# ProPrj_PocketEPD.net
KiCad netlist of a schematic drawn in EasyEDA Pro
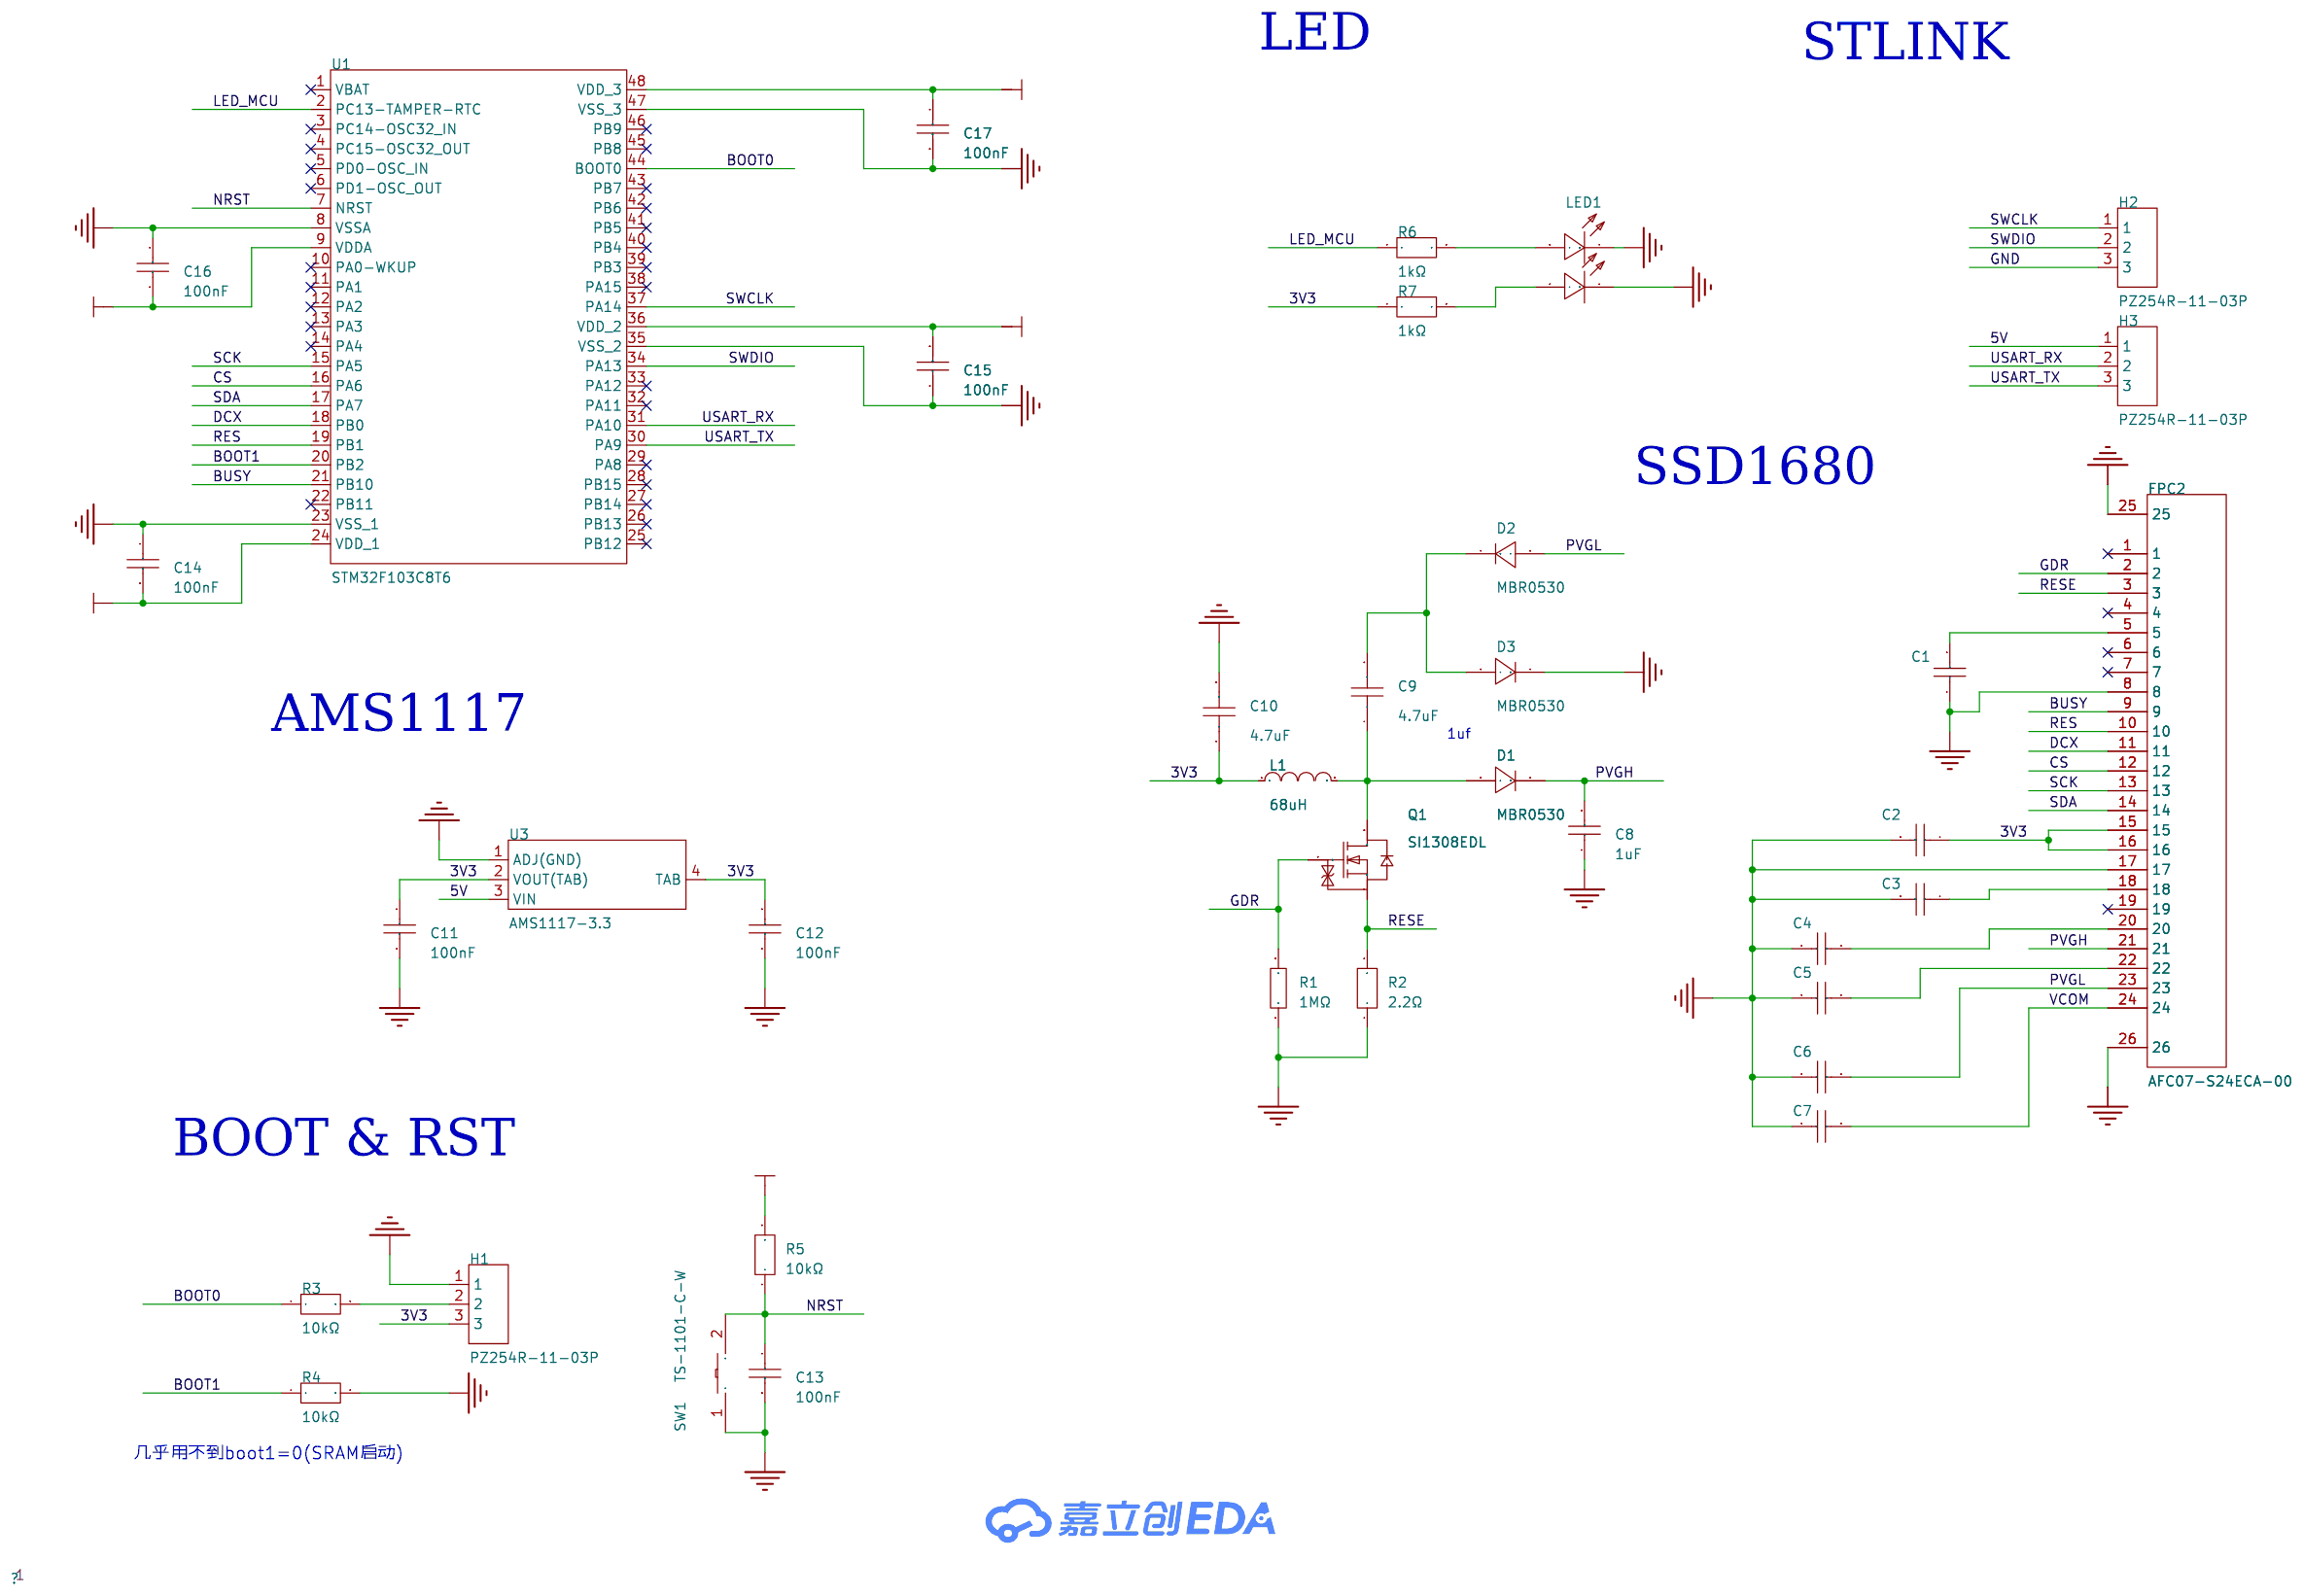
[diagram p0: schematic sheet]

(export (version "E")
  (design (tool "Eeschema 10.0.6"))
  (components
    (comp (ref "C1")
      (value "1uF")
      (footprint "easyedapro:C1206")
      (description "容值:1uF;精度:±10%;额定电压:25V;温度系数:X7R;")
      (fields
        (field (name "Manufacturer Part") "CL31B105KAHNNNE")
        (field (name "Manufacturer") "SAMSUNG(三星)")
      )
      (libsource (lib "easyedapro") (part "CL31B105KAHNNNE"))
    )
    (comp (ref "C2")
      (value "1uF")
      (footprint "easyedapro:C1206")
      (description "容值:1uF;精度:±10%;额定电压:25V;温度系数:X7R;")
      (fields
        (field (name "Manufacturer Part") "CL31B105KAHNNNE")
        (field (name "Manufacturer") "SAMSUNG(三星)")
      )
      (libsource (lib "easyedapro") (part "CL31B105KAHNNNE"))
    )
    (comp (ref "C3")
      (value "1uF")
      (footprint "easyedapro:C1206")
      (description "容值:1uF;精度:±10%;额定电压:25V;温度系数:X7R;")
      (fields
        (field (name "Manufacturer Part") "CL31B105KAHNNNE")
        (field (name "Manufacturer") "SAMSUNG(三星)")
      )
      (libsource (lib "easyedapro") (part "CL31B105KAHNNNE"))
    )
    (comp (ref "C4")
      (value "1uF")
      (footprint "easyedapro:C1206")
      (description "容值:1uF;精度:±10%;额定电压:25V;温度系数:X7R;")
      (fields
        (field (name "Manufacturer Part") "CL31B105KAHNNNE")
        (field (name "Manufacturer") "SAMSUNG(三星)")
      )
      (libsource (lib "easyedapro") (part "CL31B105KAHNNNE"))
    )
    (comp (ref "C5")
      (value "1uF")
      (footprint "easyedapro:C1206")
      (description "容值:1uF;精度:±10%;额定电压:25V;温度系数:X7R;")
      (fields
        (field (name "Manufacturer Part") "CL31B105KAHNNNE")
        (field (name "Manufacturer") "SAMSUNG(三星)")
      )
      (libsource (lib "easyedapro") (part "CL31B105KAHNNNE"))
    )
    (comp (ref "C6")
      (value "1uF")
      (footprint "easyedapro:C1206")
      (description "容值:1uF;精度:±10%;额定电压:25V;温度系数:X7R;")
      (fields
        (field (name "Manufacturer Part") "CL31B105KAHNNNE")
        (field (name "Manufacturer") "SAMSUNG(三星)")
      )
      (libsource (lib "easyedapro") (part "CL31B105KAHNNNE"))
    )
    (comp (ref "C7")
      (value "1uF")
      (footprint "easyedapro:C1206")
      (description "容值:1uF;精度:±10%;额定电压:25V;温度系数:X7R;")
      (fields
        (field (name "Manufacturer Part") "CL31B105KAHNNNE")
        (field (name "Manufacturer") "SAMSUNG(三星)")
      )
      (libsource (lib "easyedapro") (part "CL31B105KAHNNNE"))
    )
    (comp (ref "C8")
      (value "1uF")
      (footprint "easyedapro:C1206")
      (description "容值:1uF;精度:±10%;额定电压:25V;温度系数:X7R;")
      (fields
        (field (name "Manufacturer Part") "CL31B105KAHNNNE")
        (field (name "Manufacturer") "SAMSUNG(三星)")
      )
      (libsource (lib "easyedapro") (part "CL31B105KAHNNNE"))
    )
    (comp (ref "C9")
      (value "4.7uF")
      (footprint "easyedapro:C1206")
      (description "容值:4.7uF;精度:±10%;额定电压:25V;温度系数:X7R;")
      (fields (field (name "Manufacturer Part") "1206B475K250NT") (field (name "Manufacturer") "FH(风华)"))
      (libsource (lib "easyedapro") (part "1206B475K250NT"))
    )
    (comp (ref "C10")
      (value "4.7uF")
      (footprint "easyedapro:C1206")
      (description "容值:4.7uF;精度:±10%;额定电压:25V;温度系数:X7R;")
      (fields (field (name "Manufacturer Part") "1206B475K250NT") (field (name "Manufacturer") "FH(风华)"))
      (libsource (lib "easyedapro") (part "1206B475K250NT"))
    )
    (comp (ref "C11")
      (value "100nF")
      (footprint "easyedapro:C1206")
      (description "容值:100nF;精度:±10%;额定电压:100V;温度系数:X7R;")
      (fields
        (field (name "Manufacturer Part") "CL31B104KCFNNNE")
        (field (name "Manufacturer") "SAMSUNG(三星)")
      )
      (libsource (lib "easyedapro") (part "CL31B104KCFNNNE"))
    )
    (comp (ref "C12")
      (value "100nF")
      (footprint "easyedapro:C1206")
      (description "容值:100nF;精度:±10%;额定电压:100V;温度系数:X7R;")
      (fields
        (field (name "Manufacturer Part") "CL31B104KCFNNNE")
        (field (name "Manufacturer") "SAMSUNG(三星)")
      )
      (libsource (lib "easyedapro") (part "CL31B104KCFNNNE"))
    )
    (comp (ref "C13")
      (value "100nF")
      (footprint "easyedapro:C1206")
      (description "容值:100nF;精度:±10%;额定电压:100V;温度系数:X7R;")
      (fields
        (field (name "Manufacturer Part") "CL31B104KCFNNNE")
        (field (name "Manufacturer") "SAMSUNG(三星)")
      )
      (libsource (lib "easyedapro") (part "CL31B104KCFNNNE"))
    )
    (comp (ref "C14")
      (value "100nF")
      (footprint "easyedapro:C1206")
      (description "容值:100nF;精度:±10%;额定电压:100V;温度系数:X7R;")
      (fields
        (field (name "Manufacturer Part") "CL31B104KCFNNNE")
        (field (name "Manufacturer") "SAMSUNG(三星)")
      )
      (libsource (lib "easyedapro") (part "CL31B104KCFNNNE"))
    )
    (comp (ref "C15")
      (value "100nF")
      (footprint "easyedapro:C1206")
      (description "容值:100nF;精度:±10%;额定电压:100V;温度系数:X7R;")
      (fields
        (field (name "Manufacturer Part") "CL31B104KCFNNNE")
        (field (name "Manufacturer") "SAMSUNG(三星)")
      )
      (libsource (lib "easyedapro") (part "CL31B104KCFNNNE"))
    )
    (comp (ref "C16")
      (value "100nF")
      (footprint "easyedapro:C1206")
      (description "容值:100nF;精度:±10%;额定电压:100V;温度系数:X7R;")
      (fields
        (field (name "Manufacturer Part") "CL31B104KCFNNNE")
        (field (name "Manufacturer") "SAMSUNG(三星)")
      )
      (libsource (lib "easyedapro") (part "CL31B104KCFNNNE"))
    )
    (comp (ref "C17")
      (value "100nF")
      (footprint "easyedapro:C1206")
      (description "容值:100nF;精度:±10%;额定电压:100V;温度系数:X7R;")
      (fields
        (field (name "Manufacturer Part") "CL31B104KCFNNNE")
        (field (name "Manufacturer") "SAMSUNG(三星)")
      )
      (libsource (lib "easyedapro") (part "CL31B104KCFNNNE"))
    )
    (comp (ref "D1")
      (value "MBR0530")
      (footprint "easyedapro:SOD-123_L2.8-W1.8-LS3.7-RD")
      (description "二极管配置:-;正向压降(Vf):550mV@500mA;直流反向耐压(Vr):30V;整流电流:500mA;")
      (fields (field (name "Manufacturer") "CJ(江苏长电/长晶)"))
      (libsource (lib "easyedapro") (part "MBR0530"))
    )
    (comp (ref "D2")
      (value "MBR0530")
      (footprint "easyedapro:SOD-123_L2.8-W1.8-LS3.7-RD")
      (description "二极管配置:-;正向压降(Vf):550mV@500mA;直流反向耐压(Vr):30V;整流电流:500mA;")
      (fields (field (name "Manufacturer") "CJ(江苏长电/长晶)"))
      (libsource (lib "easyedapro") (part "MBR0530"))
    )
    (comp (ref "D3")
      (value "MBR0530")
      (footprint "easyedapro:SOD-123_L2.8-W1.8-LS3.7-RD")
      (description "二极管配置:-;正向压降(Vf):550mV@500mA;直流反向耐压(Vr):30V;整流电流:500mA;")
      (fields (field (name "Manufacturer") "CJ(江苏长电/长晶)"))
      (libsource (lib "easyedapro") (part "MBR0530"))
    )
    (comp (ref "FPC2")
      (value "AFC07-S24ECA-00")
      (footprint "easyedapro:FPC-SMD_AFC07-S24ECA-00")
      (description "锁定特性:抽屉式;触点类型:上接;触点数量:24P;间距:0.5mm;安装类型:卧贴;")
      (fields (field (name "Manufacturer") "JS(钜硕电子)"))
      (libsource (lib "easyedapro") (part "AFC07-S24ECA-00"))
    )
    (comp (ref "H1")
      (value "PZ254R-11-03P")
      (footprint "easyedapro:HDR-TH_3P-P2.54-H-M-W10.4")
      (fields (field (name "Manufacturer") "XFCN(兴飞)"))
      (libsource (lib "easyedapro") (part "PZ254R-11-03P"))
    )
    (comp (ref "H2")
      (value "PZ254R-11-03P")
      (footprint "easyedapro:HDR-TH_3P-P2.54-H-M-W10.4")
      (fields (field (name "Manufacturer") "XFCN(兴飞)"))
      (libsource (lib "easyedapro") (part "PZ254R-11-03P"))
    )
    (comp (ref "H3")
      (value "PZ254R-11-03P")
      (footprint "easyedapro:HDR-TH_3P-P2.54-H-M-W10.4")
      (fields (field (name "Manufacturer") "XFCN(兴飞)"))
      (libsource (lib "easyedapro") (part "PZ254R-11-03P"))
    )
    (comp (ref "L1")
      (value "68uH")
      (footprint "easyedapro:IND-SMD_L4.0-W4.0_FNR40XXS")
      (description "电感值:68uH;精度:±20%;额定电流:500mA;饱和电流(Isat):670mA;类型:磁胶屏蔽绕线合金电感;")
      (fields (field (name "Manufacturer Part") "FNR4020S680MT") (field (name "Manufacturer") "cjiang(长江微电)"))
      (libsource (lib "easyedapro") (part "FNR4020S680MT"))
    )
    (comp (ref "LED1")
      (value "TJ-S3227SW1TCGLC2R6B-A5")
      (footprint "easyedapro:LED-SMD_4P-L3.2-W2.7_PD15-22C")
      (fields (field (name "Manufacturer") "TOGIALED(统佳)"))
      (libsource (lib "easyedapro") (part "TJ-S3227SW1TCGLC2R6B-A5"))
    )
    (comp (ref "Q1")
      (value "SI1308EDL")
      (footprint "easyedapro:SOT-323-3_L2.0-W1.3-P1.30-LS2.1-BR")
      (description "漏源电压(Vdss):30V;连续漏极电流(Id):1.4A;导通电阻(RDS(on)):150mΩ@4.5V,0.5A;耗散功率(Pd):360mW;阈值电压(Vgs(th)):1.5V;")
      (fields (field (name "Manufacturer") "TECH PUBLIC(台舟)"))
      (libsource (lib "easyedapro") (part "SI1308EDL_C7603347"))
    )
    (comp (ref "R1")
      (value "1MΩ")
      (footprint "easyedapro:R1206")
      (description "电阻类型:厚膜电阻;阻值:1MΩ;精度:±5%;功率:250mW;工作电压:200V;温度系数:±100ppm/°C;")
      (fields (field (name "Manufacturer Part") "FRC1206J105 TS") (field (name "Manufacturer") "FOJAN(富捷)"))
      (libsource (lib "easyedapro") (part "FRC1206J105 TS"))
    )
    (comp (ref "R2")
      (value "2.2Ω")
      (footprint "easyedapro:R1206")
      (description "电阻类型:厚膜电阻;阻值:2.2Ω;精度:±5%;功率:250mW;工作电压:200V;温度系数:±200ppm/°C;")
      (fields (field (name "Manufacturer Part") "FRC1206J2R2 TS") (field (name "Manufacturer") "FOJAN(富捷)"))
      (libsource (lib "easyedapro") (part "FRC1206J2R2 TS"))
    )
    (comp (ref "R3")
      (value "10kΩ")
      (footprint "easyedapro:R1206")
      (description "电阻类型:厚膜电阻;阻值:10kΩ;精度:±5%;功率:250mW;工作电压:200V;温度系数:±100ppm/°C;")
      (fields (field (name "Manufacturer Part") "FRC1206J103 TS") (field (name "Manufacturer") "FOJAN(富捷)"))
      (libsource (lib "easyedapro") (part "FRC1206J103 TS"))
    )
    (comp (ref "R4")
      (value "10kΩ")
      (footprint "easyedapro:R1206")
      (description "电阻类型:厚膜电阻;阻值:10kΩ;精度:±5%;功率:250mW;工作电压:200V;温度系数:±100ppm/°C;")
      (fields (field (name "Manufacturer Part") "FRC1206J103 TS") (field (name "Manufacturer") "FOJAN(富捷)"))
      (libsource (lib "easyedapro") (part "FRC1206J103 TS"))
    )
    (comp (ref "R5")
      (value "10kΩ")
      (footprint "easyedapro:R1206")
      (description "电阻类型:厚膜电阻;阻值:10kΩ;精度:±5%;功率:250mW;工作电压:200V;温度系数:±100ppm/°C;")
      (fields (field (name "Manufacturer Part") "FRC1206J103 TS") (field (name "Manufacturer") "FOJAN(富捷)"))
      (libsource (lib "easyedapro") (part "FRC1206J103 TS"))
    )
    (comp (ref "R6")
      (value "1kΩ")
      (footprint "easyedapro:R1206")
      (description "电阻类型:厚膜电阻;阻值:1kΩ;精度:±5%;功率:250mW;工作电压:200V;温度系数:±100ppm/°C;")
      (fields (field (name "Manufacturer Part") "FRC1206J102 TS") (field (name "Manufacturer") "FOJAN(富捷)"))
      (libsource (lib "easyedapro") (part "FRC1206J102 TS"))
    )
    (comp (ref "R7")
      (value "1kΩ")
      (footprint "easyedapro:R1206")
      (description "电阻类型:厚膜电阻;阻值:1kΩ;精度:±5%;功率:250mW;工作电压:200V;温度系数:±100ppm/°C;")
      (fields (field (name "Manufacturer Part") "FRC1206J102 TS") (field (name "Manufacturer") "FOJAN(富捷)"))
      (libsource (lib "easyedapro") (part "FRC1206J102 TS"))
    )
    (comp (ref "SW1")
      (value "TS-1101-C-W")
      (footprint "easyedapro:SW-SMD_L6.0-W3.3-LS8.0")
      (fields (field (name "Manufacturer") "XKB Connectivity(中国星坤)"))
      (libsource (lib "easyedapro") (part "TS-1101-C-W"))
    )
    (comp (ref "U1")
      (value "STM32F103C8T6")
      (footprint "easyedapro:LQFP-48_L7.0-W7.0-P0.50-LS9.0-BL")
      (description "CPU内核:ARM-M3;CPU最大主频:72MHz;应用领域:-;")
      (fields (field (name "Manufacturer") "ST(意法半导体)"))
      (libsource (lib "easyedapro") (part "STM32F103C8T6"))
    )
    (comp (ref "U3")
      (value "AMS1117-3.3")
      (footprint "easyedapro:SOT-223-4_L6.5-W3.5-P2.30-LS7.0-BR")
      (description "输出类型:固定;工作电压:12V;输出电压:3.3V;输出电流:1A;电源纹波抑制比(PSRR):60dB@(120Hz);输出极性:正极;")
      (fields (field (name "Manufacturer") "UMW(友台半导体)"))
      (libsource (lib "easyedapro") (part "AMS1117-3.3_C347222"))
    )
  )
  (nets
    (net (code "1") (name "/5V") (class "Default")
      (node (ref "H3") (pin "1") (pinfunction "1_1") (pintype "unspecified"))
      (node (ref "U3") (pin "3") (pinfunction "VIN_3") (pintype "unspecified"))
    )
    (net (code "2") (name "/BOOT0") (class "Default")
      (node (ref "R3") (pin "1") (pinfunction "1_1") (pintype "unspecified"))
      (node (ref "U1") (pin "44") (pinfunction "BOOT0_44") (pintype "unspecified"))
    )
    (net (code "3") (name "/BOOT1") (class "Default")
      (node (ref "R4") (pin "1") (pinfunction "1_1") (pintype "unspecified"))
      (node (ref "U1") (pin "20") (pinfunction "PB2_20") (pintype "unspecified"))
    )
    (net (code "4") (name "/BUSY") (class "Default")
      (node (ref "FPC2") (pin "9") (pinfunction "9_9") (pintype "unspecified"))
      (node (ref "U1") (pin "21") (pinfunction "PB10_21") (pintype "unspecified"))
    )
    (net (code "5") (name "/CS") (class "Default")
      (node (ref "FPC2") (pin "12") (pinfunction "12_12") (pintype "unspecified"))
      (node (ref "U1") (pin "16") (pinfunction "PA6_16") (pintype "unspecified"))
    )
    (net (code "6") (name "/DCX") (class "Default")
      (node (ref "FPC2") (pin "11") (pinfunction "11_11") (pintype "unspecified"))
      (node (ref "U1") (pin "18") (pinfunction "PB0_18") (pintype "unspecified"))
    )
    (net (code "7") (name "/GDR") (class "Default")
      (node (ref "FPC2") (pin "2") (pinfunction "2_2") (pintype "unspecified"))
      (node (ref "Q1") (pin "1") (pinfunction "G_1") (pintype "unspecified"))
      (node (ref "R1") (pin "2") (pinfunction "2_2") (pintype "unspecified"))
    )
    (net (code "8") (name "/LED_MCU") (class "Default")
      (node (ref "R6") (pin "1") (pinfunction "1_1") (pintype "unspecified"))
      (node (ref "U1") (pin "2") (pinfunction "PC13-TAMPER-RTC_2") (pintype "unspecified"))
    )
    (net (code "9") (name "/NRST") (class "Default")
      (node (ref "C13") (pin "1") (pinfunction "1_1") (pintype "input"))
      (node (ref "R5") (pin "1") (pinfunction "1_1") (pintype "unspecified"))
      (node (ref "SW1") (pin "2") (pinfunction "2_2") (pintype "unspecified"))
      (node (ref "U1") (pin "7") (pinfunction "NRST_7") (pintype "unspecified"))
    )
    (net (code "10") (name "/PVGH") (class "Default")
      (node (ref "C8") (pin "2") (pinfunction "2_2") (pintype "input"))
      (node (ref "D1") (pin "1") (pinfunction "C_1") (pintype "unspecified"))
      (node (ref "FPC2") (pin "21") (pinfunction "21_21") (pintype "unspecified"))
    )
    (net (code "11") (name "/PVGL") (class "Default")
      (node (ref "C6") (pin "1") (pinfunction "1_1") (pintype "input"))
      (node (ref "D2") (pin "2") (pinfunction "A_2") (pintype "unspecified"))
      (node (ref "FPC2") (pin "23") (pinfunction "23_23") (pintype "unspecified"))
    )
    (net (code "12") (name "/RES") (class "Default")
      (node (ref "FPC2") (pin "10") (pinfunction "10_10") (pintype "unspecified"))
      (node (ref "U1") (pin "19") (pinfunction "PB1_19") (pintype "unspecified"))
    )
    (net (code "13") (name "/RESE") (class "Default")
      (node (ref "FPC2") (pin "3") (pinfunction "3_3") (pintype "unspecified"))
      (node (ref "Q1") (pin "2") (pinfunction "S_2") (pintype "unspecified"))
      (node (ref "R2") (pin "2") (pinfunction "2_2") (pintype "unspecified"))
    )
    (net (code "14") (name "/SCK") (class "Default")
      (node (ref "FPC2") (pin "13") (pinfunction "13_13") (pintype "unspecified"))
      (node (ref "U1") (pin "15") (pinfunction "PA5_15") (pintype "unspecified"))
    )
    (net (code "15") (name "/SDA") (class "Default")
      (node (ref "FPC2") (pin "14") (pinfunction "14_14") (pintype "unspecified"))
      (node (ref "U1") (pin "17") (pinfunction "PA7_17") (pintype "unspecified"))
    )
    (net (code "16") (name "/SWCLK") (class "Default")
      (node (ref "H2") (pin "1") (pinfunction "1_1") (pintype "unspecified"))
      (node (ref "U1") (pin "37") (pinfunction "PA14_37") (pintype "unspecified"))
    )
    (net (code "17") (name "/SWDIO") (class "Default")
      (node (ref "H2") (pin "2") (pinfunction "2_2") (pintype "unspecified"))
      (node (ref "U1") (pin "34") (pinfunction "PA13_34") (pintype "unspecified"))
    )
    (net (code "18") (name "/USART_RX") (class "Default")
      (node (ref "H3") (pin "2") (pinfunction "2_2") (pintype "unspecified"))
      (node (ref "U1") (pin "31") (pinfunction "PA10_31") (pintype "unspecified"))
    )
    (net (code "19") (name "/USART_TX") (class "Default")
      (node (ref "H3") (pin "3") (pinfunction "3_3") (pintype "unspecified"))
      (node (ref "U1") (pin "30") (pinfunction "PA9_30") (pintype "unspecified"))
    )
    (net (code "20") (name "/VCOM") (class "Default")
      (node (ref "C7") (pin "1") (pinfunction "1_1") (pintype "input"))
      (node (ref "FPC2") (pin "24") (pinfunction "24_24") (pintype "unspecified"))
    )
    (net (code "21") (name "3V3") (class "Default")
      (node (ref "C10") (pin "1") (pinfunction "1_1") (pintype "unspecified"))
      (node (ref "C11") (pin "2") (pinfunction "2_2") (pintype "input"))
      (node (ref "C12") (pin "2") (pinfunction "2_2") (pintype "input"))
      (node (ref "C14") (pin "2") (pinfunction "2_2") (pintype "input"))
      (node (ref "C15") (pin "2") (pinfunction "2_2") (pintype "input"))
      (node (ref "C16") (pin "2") (pinfunction "2_2") (pintype "input"))
      (node (ref "C17") (pin "1") (pinfunction "1_1") (pintype "input"))
      (node (ref "C2") (pin "1") (pinfunction "1_1") (pintype "input"))
      (node (ref "FPC2") (pin "15") (pinfunction "15_15") (pintype "unspecified"))
      (node (ref "FPC2") (pin "16") (pinfunction "16_16") (pintype "unspecified"))
      (node (ref "H1") (pin "3") (pinfunction "3_3") (pintype "unspecified"))
      (node (ref "L1") (pin "1") (pinfunction "1_1") (pintype "unspecified"))
      (node (ref "R5") (pin "2") (pinfunction "2_2") (pintype "unspecified"))
      (node (ref "R7") (pin "1") (pinfunction "1_1") (pintype "unspecified"))
      (node (ref "U1") (pin "24") (pinfunction "VDD_1_24") (pintype "unspecified"))
      (node (ref "U1") (pin "36") (pinfunction "VDD_2_36") (pintype "unspecified"))
      (node (ref "U1") (pin "48") (pinfunction "VDD_3_48") (pintype "unspecified"))
      (node (ref "U1") (pin "9") (pinfunction "VDDA_9") (pintype "unspecified"))
      (node (ref "U3") (pin "2") (pinfunction "VOUT(TAB)_2") (pintype "unspecified"))
      (node (ref "U3") (pin "4") (pinfunction "TAB_4") (pintype "unspecified"))
    )
    (net (code "22") (name "GND") (class "Default")
      (node (ref "C1") (pin "1") (pinfunction "1_1") (pintype "input"))
      (node (ref "C10") (pin "2") (pinfunction "2_2") (pintype "unspecified"))
      (node (ref "C11") (pin "1") (pinfunction "1_1") (pintype "input"))
      (node (ref "C12") (pin "1") (pinfunction "1_1") (pintype "input"))
      (node (ref "C13") (pin "2") (pinfunction "2_2") (pintype "input"))
      (node (ref "C14") (pin "1") (pinfunction "1_1") (pintype "input"))
      (node (ref "C15") (pin "1") (pinfunction "1_1") (pintype "input"))
      (node (ref "C16") (pin "1") (pinfunction "1_1") (pintype "input"))
      (node (ref "C17") (pin "2") (pinfunction "2_2") (pintype "input"))
      (node (ref "C2") (pin "2") (pinfunction "2_2") (pintype "input"))
      (node (ref "C3") (pin "2") (pinfunction "2_2") (pintype "input"))
      (node (ref "C4") (pin "2") (pinfunction "2_2") (pintype "input"))
      (node (ref "C5") (pin "2") (pinfunction "2_2") (pintype "input"))
      (node (ref "C6") (pin "2") (pinfunction "2_2") (pintype "input"))
      (node (ref "C7") (pin "2") (pinfunction "2_2") (pintype "input"))
      (node (ref "C8") (pin "1") (pinfunction "1_1") (pintype "input"))
      (node (ref "D3") (pin "1") (pinfunction "C_1") (pintype "unspecified"))
      (node (ref "FPC2") (pin "17") (pinfunction "17_17") (pintype "unspecified"))
      (node (ref "FPC2") (pin "25") (pinfunction "25_25") (pintype "unspecified"))
      (node (ref "FPC2") (pin "26") (pinfunction "26_26") (pintype "unspecified"))
      (node (ref "FPC2") (pin "8") (pinfunction "8_8") (pintype "unspecified"))
      (node (ref "H1") (pin "1") (pinfunction "1_1") (pintype "unspecified"))
      (node (ref "H2") (pin "3") (pinfunction "3_3") (pintype "unspecified"))
      (node (ref "LED1") (pin "1") (pinfunction "C_1") (pintype "unspecified"))
      (node (ref "LED1") (pin "4") (pinfunction "C_4") (pintype "unspecified"))
      (node (ref "R1") (pin "1") (pinfunction "1_1") (pintype "unspecified"))
      (node (ref "R2") (pin "1") (pinfunction "1_1") (pintype "unspecified"))
      (node (ref "R4") (pin "2") (pinfunction "2_2") (pintype "unspecified"))
      (node (ref "SW1") (pin "1") (pinfunction "1_1") (pintype "unspecified"))
      (node (ref "U1") (pin "23") (pinfunction "VSS_1_23") (pintype "unspecified"))
      (node (ref "U1") (pin "35") (pinfunction "VSS_2_35") (pintype "unspecified"))
      (node (ref "U1") (pin "47") (pinfunction "VSS_3_47") (pintype "unspecified"))
      (node (ref "U1") (pin "8") (pinfunction "VSSA_8") (pintype "unspecified"))
      (node (ref "U3") (pin "1") (pinfunction "ADJ(GND)_1") (pintype "unspecified"))
    )
    (net (code "23") (name "Net-(C1-Pad2)") (class "Default")
      (node (ref "C1") (pin "2") (pinfunction "2_2") (pintype "input"))
      (node (ref "FPC2") (pin "5") (pinfunction "5_5") (pintype "unspecified"))
    )
    (net (code "24") (name "Net-(C3-Pad1)") (class "Default")
      (node (ref "C3") (pin "1") (pinfunction "1_1") (pintype "input"))
      (node (ref "FPC2") (pin "18") (pinfunction "18_18") (pintype "unspecified"))
    )
    (net (code "25") (name "Net-(C4-Pad1)") (class "Default")
      (node (ref "C4") (pin "1") (pinfunction "1_1") (pintype "input"))
      (node (ref "FPC2") (pin "20") (pinfunction "20_20") (pintype "unspecified"))
    )
    (net (code "26") (name "Net-(C5-Pad1)") (class "Default")
      (node (ref "C5") (pin "1") (pinfunction "1_1") (pintype "input"))
      (node (ref "FPC2") (pin "22") (pinfunction "22_22") (pintype "unspecified"))
    )
    (net (code "27") (name "Net-(D1-A)") (class "Default")
      (node (ref "C9") (pin "1") (pinfunction "1_1") (pintype "unspecified"))
      (node (ref "D1") (pin "2") (pinfunction "A_2") (pintype "unspecified"))
      (node (ref "L1") (pin "2") (pinfunction "2_2") (pintype "unspecified"))
      (node (ref "Q1") (pin "3") (pinfunction "D_3") (pintype "unspecified"))
    )
    (net (code "28") (name "Net-(D2-C)") (class "Default")
      (node (ref "C9") (pin "2") (pinfunction "2_2") (pintype "unspecified"))
      (node (ref "D2") (pin "1") (pinfunction "C_1") (pintype "unspecified"))
      (node (ref "D3") (pin "2") (pinfunction "A_2") (pintype "unspecified"))
    )
    (net (code "29") (name "Net-(H1-Pad2)") (class "Default")
      (node (ref "H1") (pin "2") (pinfunction "2_2") (pintype "unspecified"))
      (node (ref "R3") (pin "2") (pinfunction "2_2") (pintype "unspecified"))
    )
    (net (code "30") (name "Net-(LED1-A-Pad2)") (class "Default")
      (node (ref "LED1") (pin "2") (pinfunction "A_2") (pintype "unspecified"))
      (node (ref "R7") (pin "2") (pinfunction "2_2") (pintype "unspecified"))
    )
    (net (code "31") (name "Net-(LED1-A-Pad3)") (class "Default")
      (node (ref "LED1") (pin "3") (pinfunction "A_3") (pintype "unspecified"))
      (node (ref "R6") (pin "2") (pinfunction "2_2") (pintype "unspecified"))
    )
    (net (code "32") (name "unconnected-(FPC2-Pad1)") (class "Default")
      (node (ref "FPC2") (pin "1") (pinfunction "1_1") (pintype "unspecified+no_connect"))
    )
    (net (code "33") (name "unconnected-(FPC2-Pad4)") (class "Default")
      (node (ref "FPC2") (pin "4") (pinfunction "4_4") (pintype "unspecified+no_connect"))
    )
    (net (code "34") (name "unconnected-(FPC2-Pad6)") (class "Default")
      (node (ref "FPC2") (pin "6") (pinfunction "6_6") (pintype "unspecified+no_connect"))
    )
    (net (code "35") (name "unconnected-(FPC2-Pad7)") (class "Default")
      (node (ref "FPC2") (pin "7") (pinfunction "7_7") (pintype "unspecified+no_connect"))
    )
    (net (code "36") (name "unconnected-(FPC2-Pad19)") (class "Default")
      (node (ref "FPC2") (pin "19") (pinfunction "19_19") (pintype "unspecified+no_connect"))
    )
    (net (code "37") (name "unconnected-(U1-PA0-WKUP-Pad10)") (class "Default")
      (node (ref "U1") (pin "10") (pinfunction "PA0-WKUP_10") (pintype "unspecified+no_connect"))
    )
    (net (code "38") (name "unconnected-(U1-PA1-Pad11)") (class "Default")
      (node (ref "U1") (pin "11") (pinfunction "PA1_11") (pintype "unspecified+no_connect"))
    )
    (net (code "39") (name "unconnected-(U1-PA2-Pad12)") (class "Default")
      (node (ref "U1") (pin "12") (pinfunction "PA2_12") (pintype "unspecified+no_connect"))
    )
    (net (code "40") (name "unconnected-(U1-PA3-Pad13)") (class "Default")
      (node (ref "U1") (pin "13") (pinfunction "PA3_13") (pintype "unspecified+no_connect"))
    )
    (net (code "41") (name "unconnected-(U1-PA4-Pad14)") (class "Default")
      (node (ref "U1") (pin "14") (pinfunction "PA4_14") (pintype "unspecified+no_connect"))
    )
    (net (code "42") (name "unconnected-(U1-PA8-Pad29)") (class "Default")
      (node (ref "U1") (pin "29") (pinfunction "PA8_29") (pintype "unspecified+no_connect"))
    )
    (net (code "43") (name "unconnected-(U1-PA11-Pad32)") (class "Default")
      (node (ref "U1") (pin "32") (pinfunction "PA11_32") (pintype "unspecified+no_connect"))
    )
    (net (code "44") (name "unconnected-(U1-PA12-Pad33)") (class "Default")
      (node (ref "U1") (pin "33") (pinfunction "PA12_33") (pintype "unspecified+no_connect"))
    )
    (net (code "45") (name "unconnected-(U1-PA15-Pad38)") (class "Default")
      (node (ref "U1") (pin "38") (pinfunction "PA15_38") (pintype "unspecified+no_connect"))
    )
    (net (code "46") (name "unconnected-(U1-PB3-Pad39)") (class "Default")
      (node (ref "U1") (pin "39") (pinfunction "PB3_39") (pintype "unspecified+no_connect"))
    )
    (net (code "47") (name "unconnected-(U1-PB4-Pad40)") (class "Default")
      (node (ref "U1") (pin "40") (pinfunction "PB4_40") (pintype "unspecified+no_connect"))
    )
    (net (code "48") (name "unconnected-(U1-PB5-Pad41)") (class "Default")
      (node (ref "U1") (pin "41") (pinfunction "PB5_41") (pintype "unspecified+no_connect"))
    )
    (net (code "49") (name "unconnected-(U1-PB6-Pad42)") (class "Default")
      (node (ref "U1") (pin "42") (pinfunction "PB6_42") (pintype "unspecified+no_connect"))
    )
    (net (code "50") (name "unconnected-(U1-PB7-Pad43)") (class "Default")
      (node (ref "U1") (pin "43") (pinfunction "PB7_43") (pintype "unspecified+no_connect"))
    )
    (net (code "51") (name "unconnected-(U1-PB8-Pad45)") (class "Default")
      (node (ref "U1") (pin "45") (pinfunction "PB8_45") (pintype "unspecified+no_connect"))
    )
    (net (code "52") (name "unconnected-(U1-PB9-Pad46)") (class "Default")
      (node (ref "U1") (pin "46") (pinfunction "PB9_46") (pintype "unspecified+no_connect"))
    )
    (net (code "53") (name "unconnected-(U1-PB11-Pad22)") (class "Default")
      (node (ref "U1") (pin "22") (pinfunction "PB11_22") (pintype "unspecified+no_connect"))
    )
    (net (code "54") (name "unconnected-(U1-PB12-Pad25)") (class "Default")
      (node (ref "U1") (pin "25") (pinfunction "PB12_25") (pintype "unspecified+no_connect"))
    )
    (net (code "55") (name "unconnected-(U1-PB13-Pad26)") (class "Default")
      (node (ref "U1") (pin "26") (pinfunction "PB13_26") (pintype "unspecified+no_connect"))
    )
    (net (code "56") (name "unconnected-(U1-PB14-Pad27)") (class "Default")
      (node (ref "U1") (pin "27") (pinfunction "PB14_27") (pintype "unspecified+no_connect"))
    )
    (net (code "57") (name "unconnected-(U1-PB15-Pad28)") (class "Default")
      (node (ref "U1") (pin "28") (pinfunction "PB15_28") (pintype "unspecified+no_connect"))
    )
    (net (code "58") (name "unconnected-(U1-PC14-OSC32_IN-Pad3)") (class "Default")
      (node (ref "U1") (pin "3") (pinfunction "PC14-OSC32_IN_3") (pintype "unspecified+no_connect"))
    )
    (net (code "59") (name "unconnected-(U1-PC15-OSC32_OUT-Pad4)") (class "Default")
      (node (ref "U1") (pin "4") (pinfunction "PC15-OSC32_OUT_4") (pintype "unspecified+no_connect"))
    )
    (net (code "60") (name "unconnected-(U1-PD0-OSC_IN-Pad5)") (class "Default")
      (node (ref "U1") (pin "5") (pinfunction "PD0-OSC_IN_5") (pintype "unspecified+no_connect"))
    )
    (net (code "61") (name "unconnected-(U1-PD1-OSC_OUT-Pad6)") (class "Default")
      (node (ref "U1") (pin "6") (pinfunction "PD1-OSC_OUT_6") (pintype "unspecified+no_connect"))
    )
    (net (code "62") (name "unconnected-(U1-VBAT-Pad1)") (class "Default")
      (node (ref "U1") (pin "1") (pinfunction "VBAT_1") (pintype "unspecified+no_connect"))
    )
  )
)
